# Interface.net
KiCad netlist of a schematic drawn in Altium Designer
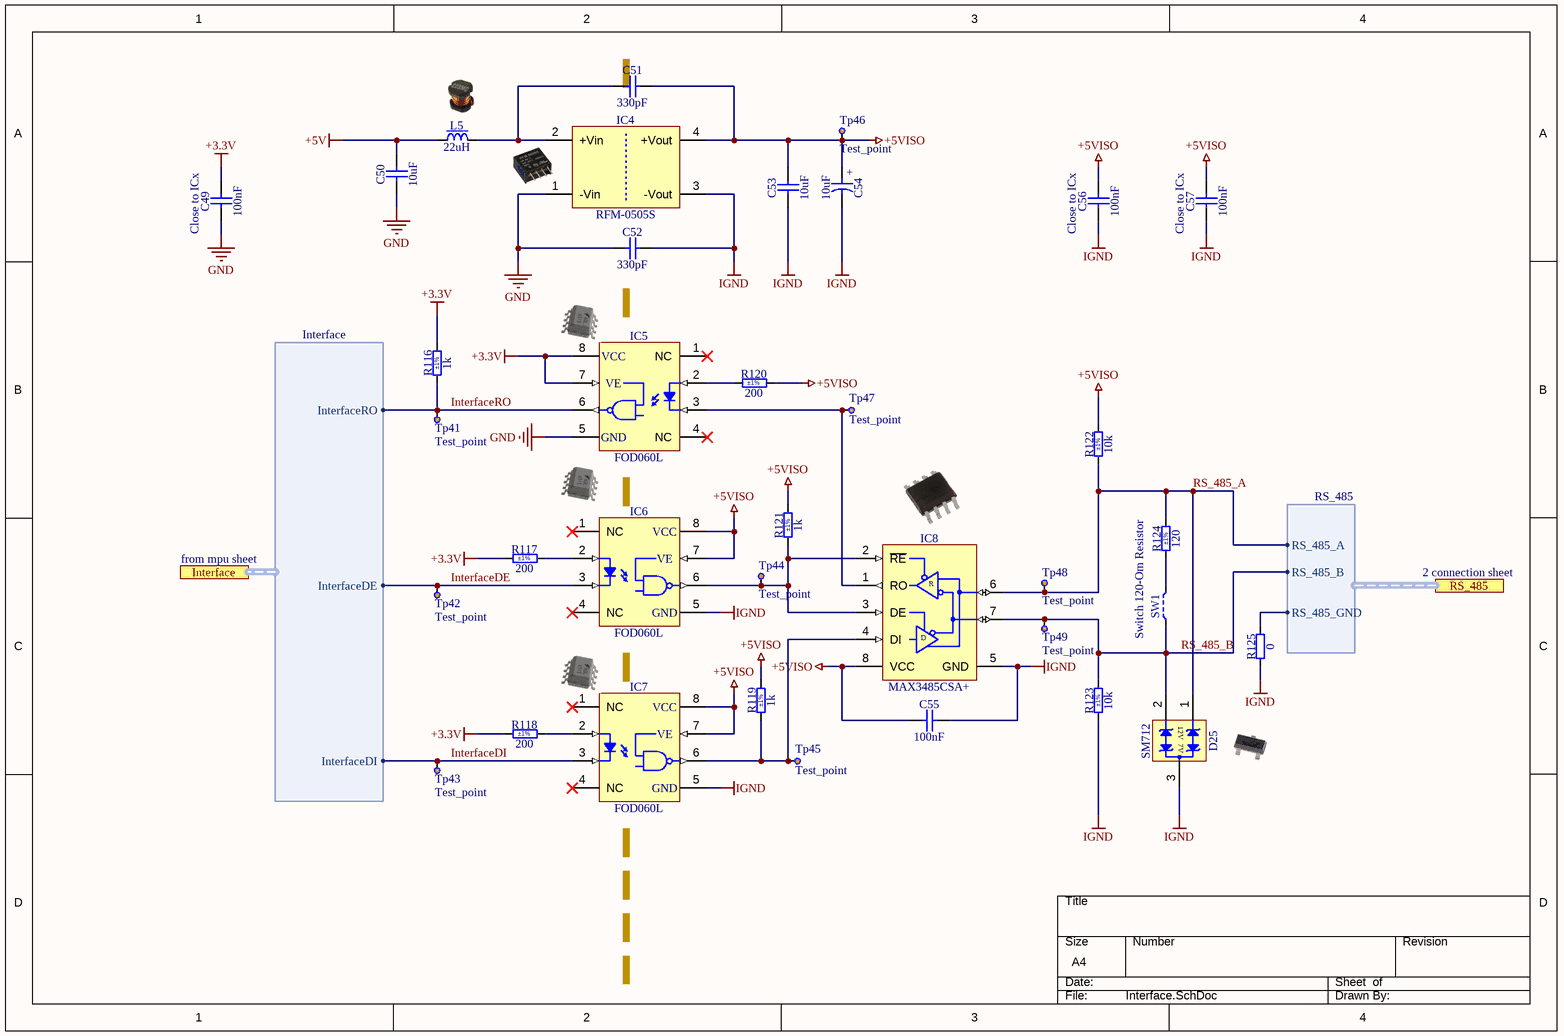
[diagram p0: Interface.SchDoc]

(export (version "E")
  (design (tool "Eeschema 10.0.6"))
  (components
    (comp (ref "C49")
      (value "100nF")
      (footprint "CAPC1608X87N")
      (description "Non-polarised capacitor")
      (fields
        (field (name "PART NUMBER") "CC0603_100NF_50V_10%_X7R")
        (field (name "VOLTAGE") "50V")
        (field (name "AUTHOR") "CERN DEM JLC")
      )
      (libsource (lib "Capacitors") (part "Capacitor - non polarized"))
    )
    (comp (ref "C50")
      (value "10uF")
      (footprint "CAPC3216X140N")
      (description "Non-polarised capacitor")
      (fields
        (field (name "PART NUMBER") "CC1206_10UF_16V_10%_X7R")
        (field (name "VOLTAGE") "16V")
        (field (name "AUTHOR") "CERN DEM JLC")
      )
      (libsource (lib "Capacitors") (part "Capacitor - non polarized"))
    )
    (comp (ref "C51")
      (value "330pF")
      (footprint "CAPC4620X220N")
      (description "Non-polarised capacitor")
      (fields
        (field (name "PART NUMBER") "CC1808_330PF_3KV_10%_X7R")
        (field (name "VOLTAGE") "3kV")
        (field (name "AUTHOR") "CERN DEM MR")
      )
      (libsource (lib "Capacitors") (part "Capacitor - non polarized"))
    )
    (comp (ref "C52")
      (value "330pF")
      (footprint "CAPC4620X220N")
      (description "Non-polarised capacitor")
      (fields
        (field (name "PART NUMBER") "CC1808_330PF_3KV_10%_X7R")
        (field (name "VOLTAGE") "3kV")
        (field (name "AUTHOR") "CERN DEM MR")
      )
      (libsource (lib "Capacitors") (part "Capacitor - non polarized"))
    )
    (comp (ref "C53")
      (value "10uF")
      (footprint "CAPC3216X140N")
      (description "Non-polarised capacitor")
      (fields
        (field (name "PART NUMBER") "CC1206_10UF_16V_10%_X7R")
        (field (name "VOLTAGE") "16V")
        (field (name "AUTHOR") "CERN DEM JLC")
      )
      (libsource (lib "Capacitors") (part "Capacitor - non polarized"))
    )
    (comp (ref "C54")
      (value "10uF")
      (footprint "CAPAE430X540N")
      (description "Polarised capacitor")
      (fields
        (field (name "PART NUMBER") "CAE430-540_10UF_16V_20%")
        (field (name "VOLTAGE") "16V")
        (field (name "AUTHOR") "CERN DEM JLC")
      )
      (libsource (lib "Capacitors") (part "Capacitor - polarized"))
    )
    (comp (ref "C55")
      (value "100nF")
      (footprint "CAPC1608X87N")
      (description "Non-polarised capacitor")
      (fields
        (field (name "PART NUMBER") "CC0603_100NF_50V_10%_X7R")
        (field (name "VOLTAGE") "50V")
        (field (name "AUTHOR") "CERN DEM JLC")
      )
      (libsource (lib "Capacitors") (part "Capacitor - non polarized"))
    )
    (comp (ref "C56")
      (value "100nF")
      (footprint "CAPC1608X87N")
      (description "Non-polarised capacitor")
      (fields
        (field (name "PART NUMBER") "CC0603_100NF_50V_10%_X7R")
        (field (name "VOLTAGE") "50V")
        (field (name "AUTHOR") "CERN DEM JLC")
      )
      (libsource (lib "Capacitors") (part "Capacitor - non polarized"))
    )
    (comp (ref "C57")
      (value "100nF")
      (footprint "CAPC1608X87N")
      (description "Non-polarised capacitor")
      (fields
        (field (name "PART NUMBER") "CC0603_100NF_50V_10%_X7R")
        (field (name "VOLTAGE") "50V")
        (field (name "AUTHOR") "CERN DEM JLC")
      )
      (libsource (lib "Capacitors") (part "Capacitor - non polarized"))
    )
    (comp (ref "D25")
      (value "SM712")
      (footprint "SOT95P237X112-3N")
      (description "Asymmetrical TVS Diode for Extended Common-Mode RS-485")
      (fields
        (field (name "VOLTAGE") "12V/-7V")
        (field (name "POWER") "400W")
        (field (name "AUTHOR") "CERN DEM JLC")
      )
      (libsource (lib "ICs And Semiconductors") (part "SM712"))
    )
    (comp (ref "IC4")
      (value "RFM-0505S")
      (footprint "DCDC_RECOM_RFM")
      (description "RECOM, RFM Serie, Single Output DCDC Converter")
      (fields (field (name "MANUFACTURER") "RECOM") (field (name "AUTHOR") "CERN DEM BC"))
      (libsource (lib "ICs And Semiconductors") (part "DCDC_RECOM_RFM_Single Output"))
    )
    (comp (ref "IC5")
      (value "FOD060L")
      (footprint "SOIC127P594X363-8N")
      (description "Single Optocoupler")
      (fields (field (name "MANUFACTURER") "FAIRCHILD SEMICONDUCTOR") (field (name "AUTHOR") "CERN DEM JLC"))
      (libsource (lib "") (part "Optocoupler Type13_1"))
    )
    (comp (ref "IC6")
      (value "FOD060L")
      (footprint "SOIC127P594X363-8N")
      (description "Single Optocoupler")
      (fields (field (name "MANUFACTURER") "FAIRCHILD SEMICONDUCTOR") (field (name "AUTHOR") "CERN DEM JLC"))
      (libsource (lib "ICs And Semiconductors") (part "Optocoupler Type13"))
    )
    (comp (ref "IC7")
      (value "FOD060L")
      (footprint "SOIC127P594X363-8N")
      (description "Single Optocoupler")
      (fields (field (name "MANUFACTURER") "FAIRCHILD SEMICONDUCTOR") (field (name "AUTHOR") "CERN DEM JLC"))
      (libsource (lib "ICs And Semiconductors") (part "Optocoupler Type13"))
    )
    (comp (ref "IC8")
      (value "MAX3485CSA+")
      (footprint "SOIC127P600X175-8N")
      (description "3.3V-Powered, ±15kV ESD-Protected, 10Mbps,True RS-485/RS-422 Half Duplex Transceiver")
      (fields (field (name "MANUFACTURER") "MAXIM") (field (name "AUTHOR") "CERN DEM JLC"))
      (libsource (lib "ICs And Semiconductors") (part "MAX3485"))
    )
    (comp (ref "L5")
      (value "22uH")
      (footprint "IND_MURATA-PS_8200")
      (description "Inductor With Core")
      (fields
        (field (name "PART NUMBER") "IND_22UH_10%_MURATA-PS_8200")
        (field (name "POWER") "320mA")
        (field (name "AUTHOR") "CERN DEM JMW")
      )
      (libsource (lib "Inductors & Transformers") (part "Inductor With Magnetic core"))
    )
    (comp (ref "R116")
      (value "1k")
      (footprint "RESC1608X55N")
      (description "Resistor - 1%")
      (fields
        (field (name "TOLERANCE") "±1%")
        (field (name "PART NUMBER") "R0603_1K_1%_0.1W_100PPM")
        (field (name "POWER") "0.1W")
        (field (name "AUTHOR") "CERN DEM JLC")
      )
      (libsource (lib "Resistors") (part "Resistor - 1%"))
    )
    (comp (ref "R117")
      (value "200")
      (footprint "RESC1608X55N")
      (description "Resistor - 1%")
      (fields
        (field (name "TOLERANCE") "±1%")
        (field (name "PART NUMBER") "R0603_200R_1%_0.1W_100PPM")
        (field (name "POWER") "0.1W")
        (field (name "AUTHOR") "CERN DEM JLC")
      )
      (libsource (lib "Resistors") (part "Resistor - 1%"))
    )
    (comp (ref "R118")
      (value "200")
      (footprint "RESC1608X55N")
      (description "Resistor - 1%")
      (fields
        (field (name "TOLERANCE") "±1%")
        (field (name "PART NUMBER") "R0603_200R_1%_0.1W_100PPM")
        (field (name "POWER") "0.1W")
        (field (name "AUTHOR") "CERN DEM JLC")
      )
      (libsource (lib "Resistors") (part "Resistor - 1%"))
    )
    (comp (ref "R119")
      (value "1k")
      (footprint "RESC1608X55N")
      (description "Resistor - 1%")
      (fields
        (field (name "TOLERANCE") "±1%")
        (field (name "PART NUMBER") "R0603_1K_1%_0.1W_100PPM")
        (field (name "POWER") "0.1W")
        (field (name "AUTHOR") "CERN DEM JLC")
      )
      (libsource (lib "Resistors") (part "Resistor - 1%"))
    )
    (comp (ref "R120")
      (value "200")
      (footprint "RESC1608X55N")
      (description "Resistor - 1%")
      (fields
        (field (name "TOLERANCE") "±1%")
        (field (name "PART NUMBER") "R0603_200R_1%_0.1W_100PPM")
        (field (name "POWER") "0.1W")
        (field (name "AUTHOR") "CERN DEM JLC")
      )
      (libsource (lib "Resistors") (part "Resistor - 1%"))
    )
    (comp (ref "R121")
      (value "1k")
      (footprint "RESC1608X55N")
      (description "Resistor - 1%")
      (fields
        (field (name "TOLERANCE") "±1%")
        (field (name "PART NUMBER") "R0603_1K_1%_0.1W_100PPM")
        (field (name "POWER") "0.1W")
        (field (name "AUTHOR") "CERN DEM JLC")
      )
      (libsource (lib "Resistors") (part "Resistor - 1%"))
    )
    (comp (ref "R122")
      (value "10k")
      (footprint "RESC1608X55N")
      (description "Resistor - 1%")
      (fields
        (field (name "TOLERANCE") "±1%")
        (field (name "PART NUMBER") "R0603_10K_1%_0.1W_100PPM")
        (field (name "POWER") "0.1W")
        (field (name "AUTHOR") "CERN DEM JLC")
      )
      (libsource (lib "Resistors") (part "Resistor - 1%"))
    )
    (comp (ref "R123")
      (value "10k")
      (footprint "RESC1608X55N")
      (description "Resistor - 1%")
      (fields
        (field (name "TOLERANCE") "±1%")
        (field (name "PART NUMBER") "R0603_10K_1%_0.1W_100PPM")
        (field (name "POWER") "0.1W")
        (field (name "AUTHOR") "CERN DEM JLC")
      )
      (libsource (lib "Resistors") (part "Resistor - 1%"))
    )
    (comp (ref "R124")
      (value "120")
      (footprint "RESC3216X65N")
      (description "Resistor - 1%")
      (fields
        (field (name "TOLERANCE") "±1%")
        (field (name "PART NUMBER") "R1206_120R_1%_0.25W_100PPM")
        (field (name "POWER") "0.25W")
        (field (name "AUTHOR") "CERN DEM JLC")
      )
      (libsource (lib "Resistors") (part "Resistor - 1%"))
    )
    (comp (ref "R125")
      (value "0")
      (footprint "RESC1608X55N")
      (description "Resistor")
      (fields
        (field (name "PART NUMBER") "R0603_0R_JUMPER")
        (field (name "MANUFACTURER") "GENERIC")
        (field (name "AUTHOR") "CERN DEM JLC")
      )
      (libsource (lib "Resistors") (part "Resistor"))
    )
    (comp (ref "SW1")
      (value "Switch")
      (footprint "JUMPSMD0805_G50")
      (description "2 SMD Pads for Bound by Solder  Drop")
      (fields
        (field (name "PART NUMBER") "JUMPSMD0805_G50")
        (field (name "MANUFACTURER") "None")
        (field (name "AUTHOR") "CERN DEM JLC")
      )
      (libsource (lib "Eletro-mechanical") (part "SMD Solder Jumper"))
    )
    (comp (ref "Tp41")
      (value "Test_point")
      (footprint "fromST:TP_C40")
      (description "Test point")
      (fields (field (name "PUBLISHER") "Altium Limited"))
      (libsource (lib "Sajad_Altium_Library") (part "Test point"))
    )
    (comp (ref "Tp42")
      (value "Test_point")
      (footprint "fromST:TP_C40")
      (description "Test point")
      (fields (field (name "PUBLISHER") "Altium Limited"))
      (libsource (lib "Sajad_Altium_Library") (part "Test point"))
    )
    (comp (ref "Tp43")
      (value "Test_point")
      (footprint "fromST:TP_C40")
      (description "Test point")
      (fields (field (name "PUBLISHER") "Altium Limited"))
      (libsource (lib "Sajad_Altium_Library") (part "Test point"))
    )
    (comp (ref "Tp44")
      (value "Test_point")
      (footprint "fromST:TP_C40")
      (description "Test point")
      (fields (field (name "PUBLISHER") "Altium Limited"))
      (libsource (lib "Sajad_Altium_Library") (part "Test point"))
    )
    (comp (ref "Tp45")
      (value "Test_point")
      (footprint "fromST:TP_C40")
      (description "Test point")
      (fields (field (name "PUBLISHER") "Altium Limited"))
      (libsource (lib "Sajad_Altium_Library") (part "Test point"))
    )
    (comp (ref "Tp46")
      (value "Test_point")
      (footprint "fromST:TP_C40")
      (description "Test point")
      (fields (field (name "PUBLISHER") "Altium Limited"))
      (libsource (lib "Sajad_Altium_Library") (part "Test point"))
    )
    (comp (ref "Tp47")
      (value "Test_point")
      (footprint "fromST:TP_C40")
      (description "Test point")
      (fields (field (name "PUBLISHER") "Altium Limited"))
      (libsource (lib "Sajad_Altium_Library") (part "Test point"))
    )
    (comp (ref "Tp48")
      (value "Test_point")
      (footprint "fromST:TP_C40")
      (description "Test point")
      (fields (field (name "PUBLISHER") "Altium Limited"))
      (libsource (lib "Sajad_Altium_Library") (part "Test point"))
    )
    (comp (ref "Tp49")
      (value "Test_point")
      (footprint "fromST:TP_C40")
      (description "Test point")
      (fields (field (name "PUBLISHER") "Altium Limited"))
      (libsource (lib "Sajad_Altium_Library") (part "Test point"))
    )
  )
  (nets
    (net (code "3") (name "+3.3V") (class "Default")
      (node (ref "C49") (pin "2") (pinfunction "2_2") (pintype "passive"))
      (node (ref "IC5") (pin "7") (pinfunction "VE_7") (pintype "input"))
      (node (ref "IC5") (pin "8") (pinfunction "VCC_8") (pintype "power_in"))
      (node (ref "R116") (pin "2") (pinfunction "2_2") (pintype "passive"))
      (node (ref "R117") (pin "1") (pinfunction "1_1") (pintype "passive"))
      (node (ref "R118") (pin "1") (pinfunction "1_1") (pintype "passive"))
    )
    (net (code "4") (name "+5V") (class "Default")
      (node (ref "C50") (pin "2") (pinfunction "2_2") (pintype "passive"))
      (node (ref "L5") (pin "1") (pinfunction "1_1") (pintype "passive"))
    )
    (net (code "5") (name "+5VISO") (class "Default")
      (node (ref "C51") (pin "2") (pinfunction "2_2") (pintype "passive"))
      (node (ref "C53") (pin "2") (pinfunction "2_2") (pintype "passive"))
      (node (ref "C54") (pin "1") (pinfunction "1_1") (pintype "passive"))
      (node (ref "C55") (pin "1") (pinfunction "1_1") (pintype "passive"))
      (node (ref "C56") (pin "2") (pinfunction "2_2") (pintype "passive"))
      (node (ref "C57") (pin "2") (pinfunction "2_2") (pintype "passive"))
      (node (ref "IC4") (pin "4") (pinfunction "+Vout_4") (pintype "power_in"))
      (node (ref "IC6") (pin "7") (pinfunction "VE_7") (pintype "input"))
      (node (ref "IC6") (pin "8") (pinfunction "VCC_8") (pintype "power_in"))
      (node (ref "IC7") (pin "7") (pinfunction "VE_7") (pintype "input"))
      (node (ref "IC7") (pin "8") (pinfunction "VCC_8") (pintype "power_in"))
      (node (ref "IC8") (pin "8") (pinfunction "VCC_8") (pintype "power_in"))
      (node (ref "R119") (pin "2") (pinfunction "2_2") (pintype "passive"))
      (node (ref "R120") (pin "2") (pinfunction "2_2") (pintype "passive"))
      (node (ref "R121") (pin "2") (pinfunction "2_2") (pintype "passive"))
      (node (ref "R122") (pin "2") (pinfunction "2_2") (pintype "passive"))
      (node (ref "Tp46") (pin "1") (pinfunction "1_1") (pintype "passive"))
    )
    (net (code "6") (name "/InterfaceDE") (class "Default")
      (node (ref "IC6") (pin "3") (pinfunction "K_3") (pintype "input"))
      (node (ref "Tp42") (pin "1") (pinfunction "1_1") (pintype "passive"))
    )
    (net (code "7") (name "/InterfaceDI") (class "Default")
      (node (ref "IC7") (pin "3") (pinfunction "K_3") (pintype "input"))
      (node (ref "Tp43") (pin "1") (pinfunction "1_1") (pintype "passive"))
    )
    (net (code "8") (name "/InterfaceRO") (class "Default")
      (node (ref "IC5") (pin "6") (pinfunction "VO_6") (pintype "output"))
      (node (ref "R116") (pin "1") (pinfunction "1_1") (pintype "passive"))
      (node (ref "Tp41") (pin "1") (pinfunction "1_1") (pintype "passive"))
    )
    (net (code "9") (name "/RS_485_A") (class "Default")
      (node (ref "D25") (pin "1") (pinfunction "I/O1_1") (pintype "passive"))
      (node (ref "IC8") (pin "6") (pinfunction "A_6") (pintype "bidirectional"))
      (node (ref "R122") (pin "1") (pinfunction "1_1") (pintype "passive"))
      (node (ref "R124") (pin "2") (pinfunction "2_2") (pintype "passive"))
      (node (ref "Tp48") (pin "1") (pinfunction "1_1") (pintype "passive"))
    )
    (net (code "10") (name "/RS_485_B") (class "Default")
      (node (ref "D25") (pin "2") (pinfunction "I/O2_2") (pintype "passive"))
      (node (ref "IC8") (pin "7") (pinfunction "B_7") (pintype "bidirectional"))
      (node (ref "R123") (pin "2") (pinfunction "2_2") (pintype "passive"))
      (node (ref "SW1") (pin "1") (pinfunction "1_1") (pintype "bidirectional"))
      (node (ref "Tp49") (pin "1") (pinfunction "1_1") (pintype "passive"))
    )
    (net (code "11") (name "/RS_485_GND") (class "Default")
      (node (ref "R125") (pin "2") (pinfunction "2_2") (pintype "passive"))
    )
    (net (code "14") (name "GND") (class "Default")
      (node (ref "C49") (pin "1") (pinfunction "1_1") (pintype "passive"))
      (node (ref "C50") (pin "1") (pinfunction "1_1") (pintype "passive"))
      (node (ref "C52") (pin "1") (pinfunction "1_1") (pintype "passive"))
      (node (ref "IC4") (pin "1") (pinfunction "-Vin_1") (pintype "power_in"))
      (node (ref "IC5") (pin "5") (pinfunction "GND_5") (pintype "power_in"))
    )
    (net (code "15") (name "IGND") (class "Default")
      (node (ref "C52") (pin "2") (pinfunction "2_2") (pintype "passive"))
      (node (ref "C53") (pin "1") (pinfunction "1_1") (pintype "passive"))
      (node (ref "C54") (pin "2") (pinfunction "2_2") (pintype "passive"))
      (node (ref "C55") (pin "2") (pinfunction "2_2") (pintype "passive"))
      (node (ref "C56") (pin "1") (pinfunction "1_1") (pintype "passive"))
      (node (ref "C57") (pin "1") (pinfunction "1_1") (pintype "passive"))
      (node (ref "D25") (pin "3") (pinfunction "GND_3") (pintype "passive"))
      (node (ref "IC4") (pin "3") (pinfunction "-Vout_3") (pintype "power_in"))
      (node (ref "IC6") (pin "5") (pinfunction "GND_5") (pintype "power_in"))
      (node (ref "IC7") (pin "5") (pinfunction "GND_5") (pintype "power_in"))
      (node (ref "IC8") (pin "5") (pinfunction "GND_5") (pintype "power_in"))
      (node (ref "R123") (pin "1") (pinfunction "1_1") (pintype "passive"))
      (node (ref "R125") (pin "1") (pinfunction "1_1") (pintype "passive"))
    )
    (net (code "16") (name "Net-(IC4-+Vin)") (class "Default")
      (node (ref "C51") (pin "1") (pinfunction "1_1") (pintype "passive"))
      (node (ref "IC4") (pin "2") (pinfunction "+Vin_2") (pintype "power_in"))
      (node (ref "L5") (pin "2") (pinfunction "2_2") (pintype "passive"))
    )
    (net (code "17") (name "Net-(IC5-A)") (class "Default")
      (node (ref "IC5") (pin "2") (pinfunction "A_2") (pintype "input"))
      (node (ref "R120") (pin "1") (pinfunction "1_1") (pintype "passive"))
    )
    (net (code "18") (name "Net-(IC5-K)") (class "Default")
      (node (ref "IC5") (pin "3") (pinfunction "K_3") (pintype "input"))
      (node (ref "IC8") (pin "1") (pinfunction "RO_1") (pintype "output"))
      (node (ref "Tp47") (pin "1") (pinfunction "1_1") (pintype "passive"))
    )
    (net (code "19") (name "Net-(IC6-A)") (class "Default")
      (node (ref "IC6") (pin "2") (pinfunction "A_2") (pintype "input"))
      (node (ref "R117") (pin "2") (pinfunction "2_2") (pintype "passive"))
    )
    (net (code "20") (name "Net-(IC6-VO)") (class "Default")
      (node (ref "IC6") (pin "6") (pinfunction "VO_6") (pintype "output"))
      (node (ref "IC8") (pin "2") (pinfunction "~{RE}_2") (pintype "input"))
      (node (ref "IC8") (pin "3") (pinfunction "DE_3") (pintype "input"))
      (node (ref "R121") (pin "1") (pinfunction "1_1") (pintype "passive"))
      (node (ref "Tp44") (pin "1") (pinfunction "1_1") (pintype "passive"))
    )
    (net (code "21") (name "Net-(IC7-A)") (class "Default")
      (node (ref "IC7") (pin "2") (pinfunction "A_2") (pintype "input"))
      (node (ref "R118") (pin "2") (pinfunction "2_2") (pintype "passive"))
    )
    (net (code "22") (name "Net-(IC7-VO)") (class "Default")
      (node (ref "IC7") (pin "6") (pinfunction "VO_6") (pintype "output"))
      (node (ref "IC8") (pin "4") (pinfunction "DI_4") (pintype "input"))
      (node (ref "R119") (pin "1") (pinfunction "1_1") (pintype "passive"))
      (node (ref "Tp45") (pin "1") (pinfunction "1_1") (pintype "passive"))
    )
    (net (code "23") (name "Net-(R124-Pad1)") (class "Default")
      (node (ref "R124") (pin "1") (pinfunction "1_1") (pintype "passive"))
      (node (ref "SW1") (pin "2") (pinfunction "2_2") (pintype "bidirectional"))
    )
    (net (code "24") (name "unconnected-(IC5-NC-Pad1)") (class "Default")
      (node (ref "IC5") (pin "1") (pinfunction "NC_1") (pintype "passive+no_connect"))
    )
    (net (code "25") (name "unconnected-(IC5-NC-Pad4)") (class "Default")
      (node (ref "IC5") (pin "4") (pinfunction "NC_4") (pintype "passive+no_connect"))
    )
    (net (code "26") (name "unconnected-(IC6-NC-Pad1)") (class "Default")
      (node (ref "IC6") (pin "1") (pinfunction "NC_1") (pintype "passive+no_connect"))
    )
    (net (code "27") (name "unconnected-(IC6-NC-Pad4)") (class "Default")
      (node (ref "IC6") (pin "4") (pinfunction "NC_4") (pintype "passive+no_connect"))
    )
    (net (code "28") (name "unconnected-(IC7-NC-Pad1)") (class "Default")
      (node (ref "IC7") (pin "1") (pinfunction "NC_1") (pintype "passive+no_connect"))
    )
    (net (code "29") (name "unconnected-(IC7-NC-Pad4)") (class "Default")
      (node (ref "IC7") (pin "4") (pinfunction "NC_4") (pintype "passive+no_connect"))
    )
  )
)
